# MainMCU.net
KiCad netlist of a schematic drawn in Altium Designer
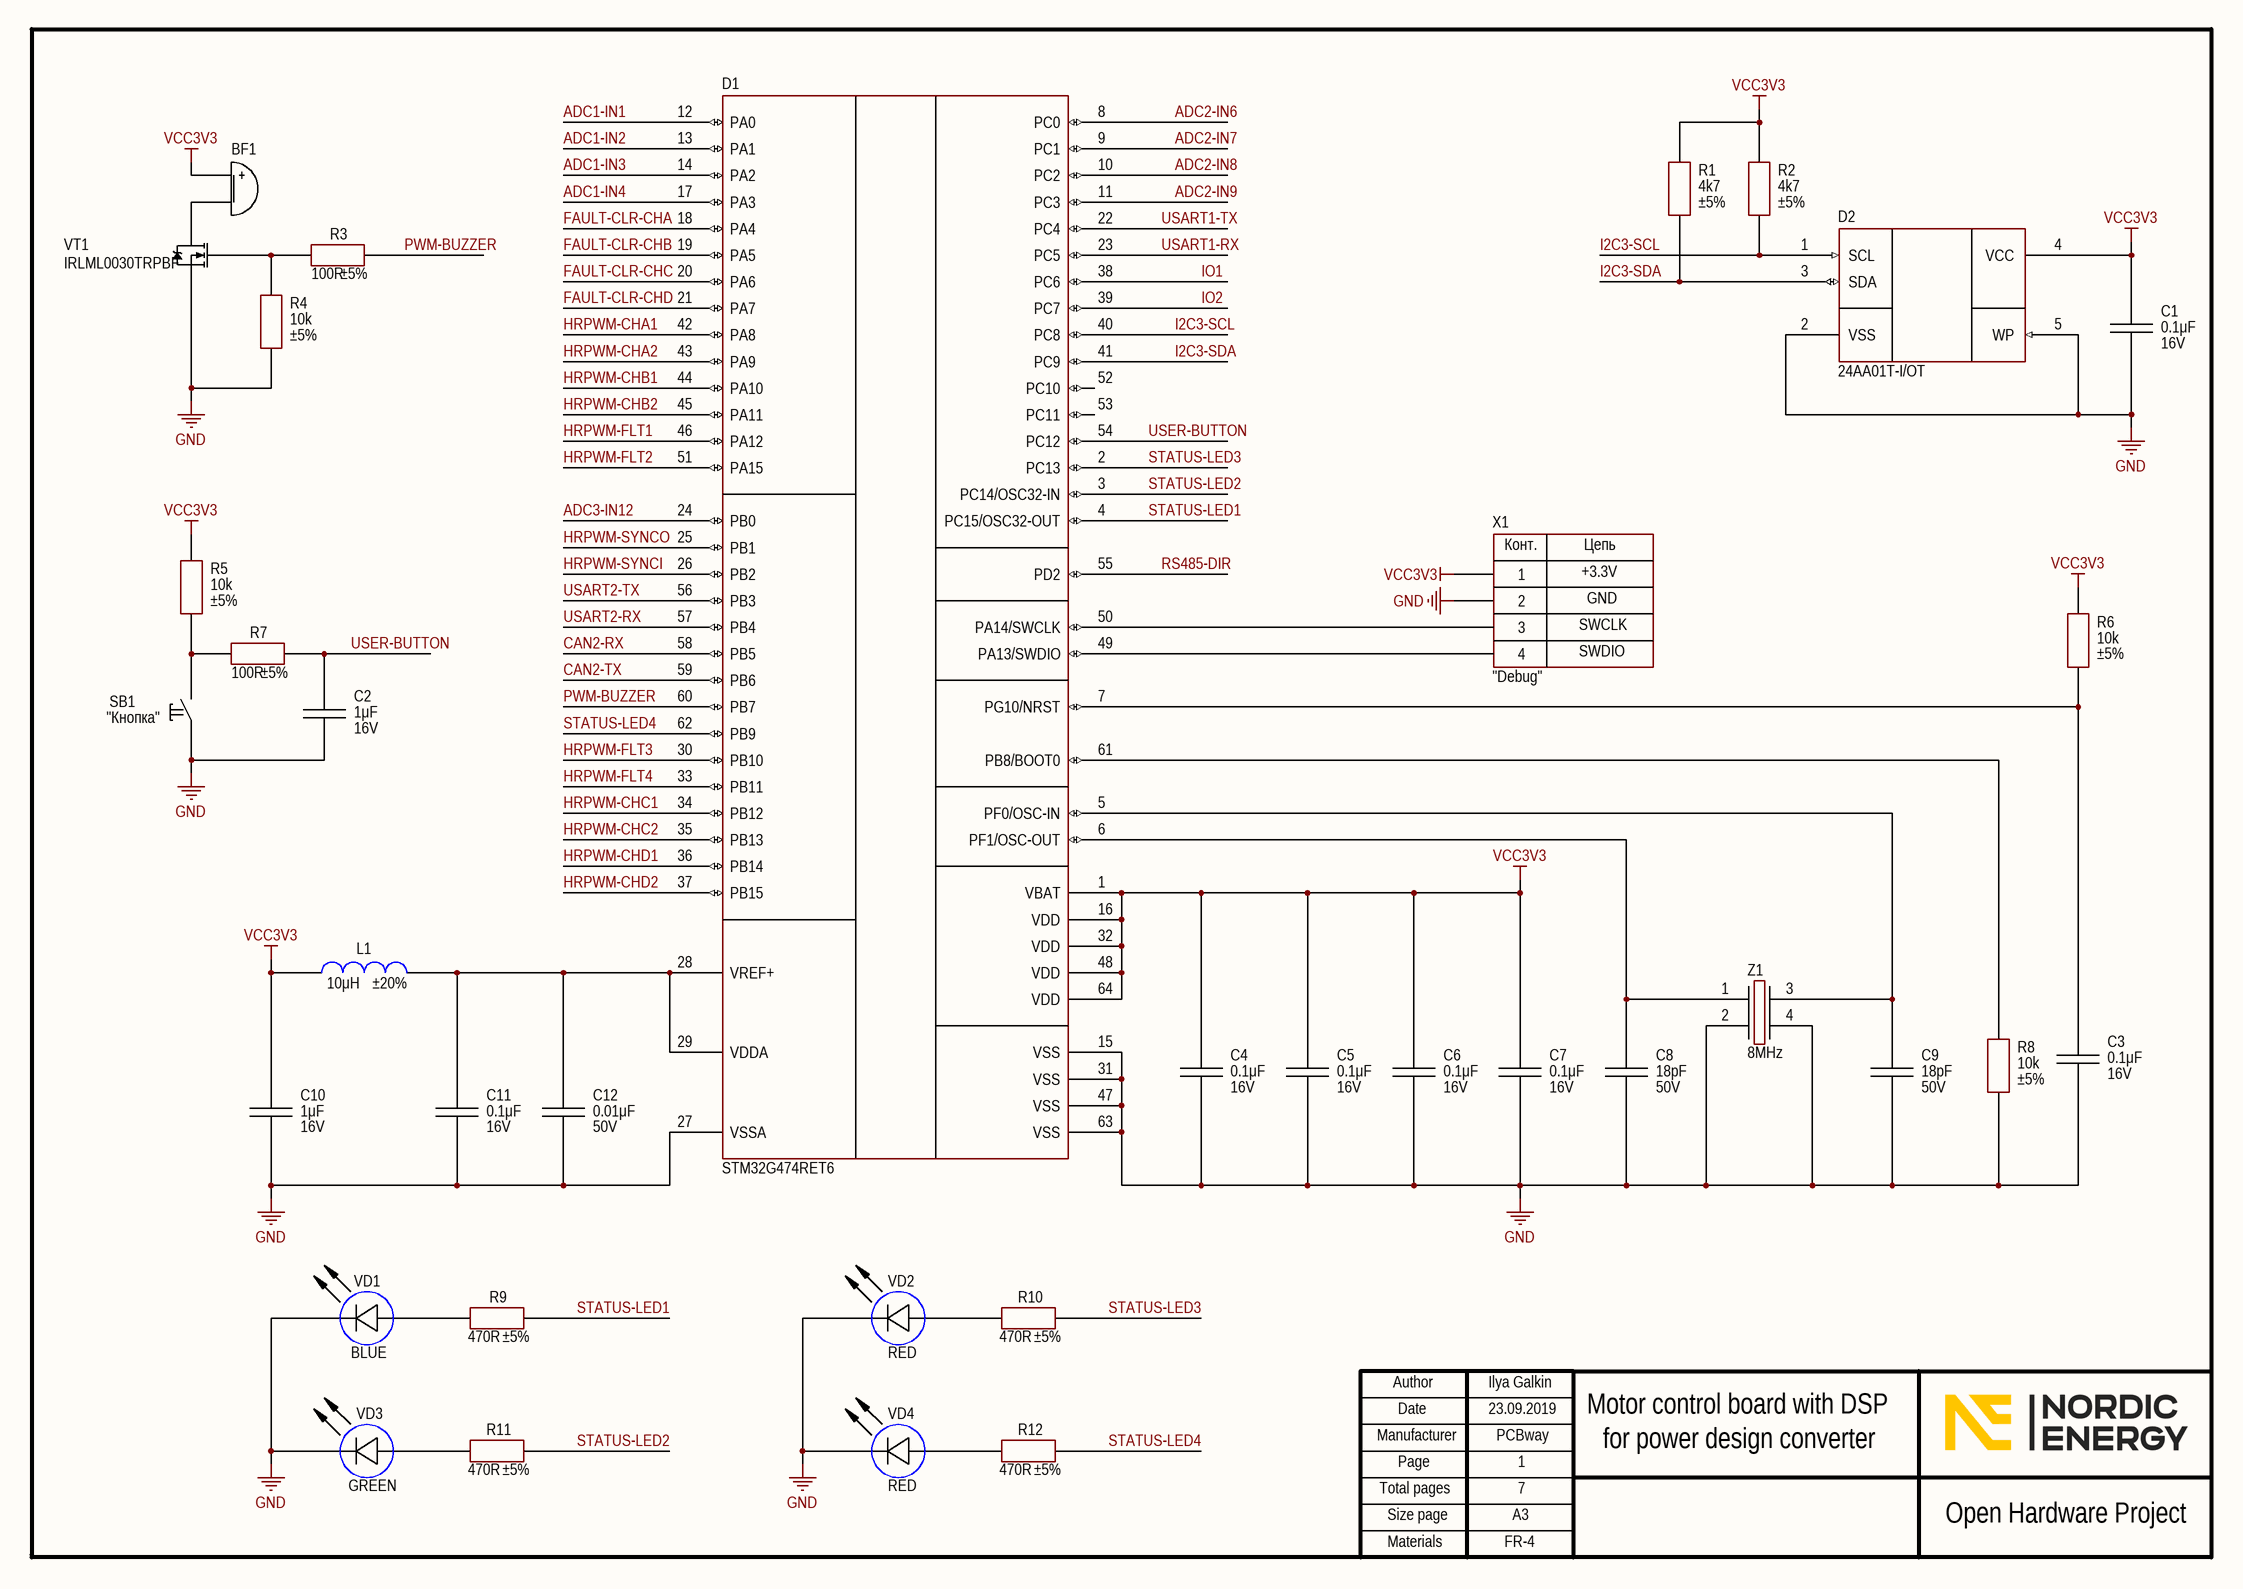
[diagram p0: MainMCU.SchDoc]

(export (version "E")
  (design (tool "Eeschema 10.0.6"))
  (components
    (comp (ref "BF1")
      (value "~")
      (footprint "BUZ: CMT-7525")
      (fields
        (field (name "MANUFACTURER") "PUI Audio")
        (field (name "VALUEMANUFACTURERPARTNUMBER") "DIP switch, 2.73 kHz, 3VDC, 80mA, -20...+70°C")
        (field (name "PARTNUMBER") "AT-0927-TT-6-R")
      )
      (libsource (lib "Electromechanics") (part "Buzzer"))
    )
    (comp (ref "C1")
      (value "0.1μF")
      (footprint "CAP: 0805")
      (fields
        (field (name "MANUFACTURER") "Yageo")
        (field (name "PARTNUMBER") "CC0805KRX7R7BB104")
        (field (name "VALUEMANUFACTURERPARTNUMBER") "Ceramic capacitor, 0.1μF, X7R, ±10%, 16V, 0805, -55...+125°C")
        (field (name "VOLTAGE") "16V")
      )
      (libsource (lib "Capacitor") (part "Ceramic_0805"))
    )
    (comp (ref "C2")
      (value "1μF")
      (footprint "CAP: 0805")
      (fields
        (field (name "MANUFACTURER") "Yageo")
        (field (name "PARTNUMBER") "CC0805KKX7R7BB105")
        (field (name "VALUEMANUFACTURERPARTNUMBER") "Ceramic capacitor, 1μF, X7R, ±10%, 16V, 0805, -55...+125°C")
        (field (name "VOLTAGE") "16V")
      )
      (libsource (lib "Capacitor") (part "Ceramic_0805"))
    )
    (comp (ref "C3")
      (value "0.1μF")
      (footprint "CAP: 0805")
      (fields
        (field (name "MANUFACTURER") "Yageo")
        (field (name "PARTNUMBER") "CC0805KRX7R7BB104")
        (field (name "VALUEMANUFACTURERPARTNUMBER") "Ceramic capacitor, 0.1μF, X7R, ±10%, 16V, 0805, -55...+125°C")
        (field (name "VOLTAGE") "16V")
      )
      (libsource (lib "Capacitor") (part "Ceramic_0805"))
    )
    (comp (ref "C4")
      (value "0.1μF")
      (footprint "CAP: 0805")
      (fields
        (field (name "MANUFACTURER") "Yageo")
        (field (name "PARTNUMBER") "CC0805KRX7R7BB104")
        (field (name "VALUEMANUFACTURERPARTNUMBER") "Ceramic capacitor, 0.1μF, X7R, ±10%, 16V, 0805, -55...+125°C")
        (field (name "VOLTAGE") "16V")
      )
      (libsource (lib "Capacitor") (part "Ceramic_0805"))
    )
    (comp (ref "C5")
      (value "0.1μF")
      (footprint "CAP: 0805")
      (fields
        (field (name "MANUFACTURER") "Yageo")
        (field (name "PARTNUMBER") "CC0805KRX7R7BB104")
        (field (name "VALUEMANUFACTURERPARTNUMBER") "Ceramic capacitor, 0.1μF, X7R, ±10%, 16V, 0805, -55...+125°C")
        (field (name "VOLTAGE") "16V")
      )
      (libsource (lib "Capacitor") (part "Ceramic_0805"))
    )
    (comp (ref "C6")
      (value "0.1μF")
      (footprint "CAP: 0805")
      (fields
        (field (name "MANUFACTURER") "Yageo")
        (field (name "PARTNUMBER") "CC0805KRX7R7BB104")
        (field (name "VALUEMANUFACTURERPARTNUMBER") "Ceramic capacitor, 0.1μF, X7R, ±10%, 16V, 0805, -55...+125°C")
        (field (name "VOLTAGE") "16V")
      )
      (libsource (lib "Capacitor") (part "Ceramic_0805"))
    )
    (comp (ref "C7")
      (value "0.1μF")
      (footprint "CAP: 0805")
      (fields
        (field (name "MANUFACTURER") "Yageo")
        (field (name "PARTNUMBER") "CC0805KRX7R7BB104")
        (field (name "VALUEMANUFACTURERPARTNUMBER") "Ceramic capacitor, 0.1μF, X7R, ±10%, 16V, 0805, -55...+125°C")
        (field (name "VOLTAGE") "16V")
      )
      (libsource (lib "Capacitor") (part "Ceramic_0805"))
    )
    (comp (ref "C8")
      (value "18pF")
      (footprint "CAP: 0805")
      (fields
        (field (name "MANUFACTURER") "Yageo")
        (field (name "PARTNUMBER") "CC0805JRNPO9BN180")
        (field (name "VALUEMANUFACTURERPARTNUMBER") "Ceramic capacitor, 18pF, NPO, ±10%, 50V, 0805, -55...+125°C")
        (field (name "VOLTAGE") "50V")
      )
      (libsource (lib "Capacitor") (part "Ceramic_0805"))
    )
    (comp (ref "C9")
      (value "18pF")
      (footprint "CAP: 0805")
      (fields
        (field (name "MANUFACTURER") "Yageo")
        (field (name "PARTNUMBER") "CC0805JRNPO9BN180")
        (field (name "VALUEMANUFACTURERPARTNUMBER") "Ceramic capacitor, 18pF, NPO, ±10%, 50V, 0805, -55...+125°C")
        (field (name "VOLTAGE") "50V")
      )
      (libsource (lib "Capacitor") (part "Ceramic_0805"))
    )
    (comp (ref "C10")
      (value "1μF")
      (footprint "CAP: 0805")
      (fields
        (field (name "MANUFACTURER") "Yageo")
        (field (name "PARTNUMBER") "CC0805KKX7R7BB105")
        (field (name "VALUEMANUFACTURERPARTNUMBER") "Ceramic capacitor, 1μF, X7R, ±10%, 16V, 0805, -55...+125°C")
        (field (name "VOLTAGE") "16V")
      )
      (libsource (lib "Capacitor") (part "Ceramic_0805"))
    )
    (comp (ref "C11")
      (value "0.1μF")
      (footprint "CAP: 0805")
      (fields
        (field (name "MANUFACTURER") "Yageo")
        (field (name "PARTNUMBER") "CC0805KRX7R7BB104")
        (field (name "VALUEMANUFACTURERPARTNUMBER") "Ceramic capacitor, 0.1μF, X7R, ±10%, 16V, 0805, -55...+125°C")
        (field (name "VOLTAGE") "16V")
      )
      (libsource (lib "Capacitor") (part "Ceramic_0805"))
    )
    (comp (ref "C12")
      (value "0.01μF")
      (footprint "CAP: 0805")
      (fields
        (field (name "MANUFACTURER") "Yageo")
        (field (name "PARTNUMBER") "CC0805KRX7R9BB103")
        (field (name "VALUEMANUFACTURERPARTNUMBER") "Ceramic capacitor, 0.01μF, X7R, ±10%, 50V, 0805, -55...+125°C")
        (field (name "VOLTAGE") "50V")
      )
      (libsource (lib "Capacitor") (part "Ceramic_0805"))
    )
    (comp (ref "D1")
      (value "~")
      (footprint "64-LQFP")
      (description "Cortex-M4")
      (fields
        (field (name "MANUFACTURER") "STMicroelectronics")
        (field (name "VALUEMANUFACTURERPARTNUMBER") "IC microcontroller, 32-Bit, Cortex-M4, 170MHz, 512KB, 128KB, 1.71...3.6V, -40...+85°C, 64-LQFP")
        (field (name "PARTNUMBER") "STM32G474RET6")
      )
      (libsource (lib "IC. MCU") (part "STM32G474RET6"))
    )
    (comp (ref "D2")
      (value "~")
      (footprint "SOT23-5")
      (description "EEPROM")
      (fields
        (field (name "MANUFACTURER") "Microchip Technology")
        (field (name "VALUEMANUFACTURERPARTNUMBER") "IC memory, EEPROM, 1KB (128x8), 400 kHz, I2C, 1.7...5.5V, -40...+85°C, SOT-23-5")
        (field (name "PARTNUMBER") "24AA01T-I/OT")
      )
      (libsource (lib "IC. Memory") (part "24AA01T"))
    )
    (comp (ref "L1")
      (value "10μH")
      (footprint "IND: 0805")
      (fields
        (field (name "MANUFACTURER") "Murata Electronics")
        (field (name "PARTNUMBER") "LQM21FN100M70L")
        (field (name "VALUEMANUFACTURERPARTNUMBER") "Fixed inductor, 10μH, ±20%, 0805, 100mA, -55...+125°C")
        (field (name "TOLERANCE") "±20%")
      )
      (libsource (lib "Inductor") (part "Inductor_0805"))
    )
    (comp (ref "R1")
      (value "4k7")
      (footprint "RES: 0805")
      (fields
        (field (name "MANUFACTURER") "Yageo")
        (field (name "PARTNUMBER") "RC0805JR-074K7L")
        (field (name "VALUEMANUFACTURERPARTNUMBER") "Resistor film, 4k7, ±5%, 0805, 0.125W, -55...+125°C")
        (field (name "TOLERANCE") "±5%")
      )
      (libsource (lib "Resistor") (part "Resistor_0805"))
    )
    (comp (ref "R2")
      (value "4k7")
      (footprint "RES: 0805")
      (fields
        (field (name "MANUFACTURER") "Yageo")
        (field (name "PARTNUMBER") "RC0805JR-074K7L")
        (field (name "VALUEMANUFACTURERPARTNUMBER") "Resistor film, 4k7, ±5%, 0805, 0.125W, -55...+125°C")
        (field (name "TOLERANCE") "±5%")
      )
      (libsource (lib "Resistor") (part "Resistor_0805"))
    )
    (comp (ref "R3")
      (value "100R")
      (footprint "RES: 0805")
      (fields
        (field (name "MANUFACTURER") "Yageo")
        (field (name "PARTNUMBER") "RC0805JR-07100RL")
        (field (name "VALUEMANUFACTURERPARTNUMBER") "Resistor film, 100R, ±5%, 0805, 0.125W, -55...+125°C")
        (field (name "TOLERANCE") "±5%")
      )
      (libsource (lib "") (part "Resistor_0805_1"))
    )
    (comp (ref "R4")
      (value "10k")
      (footprint "RES: 0805")
      (fields
        (field (name "MANUFACTURER") "Yageo")
        (field (name "PARTNUMBER") "RC0805JR-0710KL")
        (field (name "VALUEMANUFACTURERPARTNUMBER") "Resistor film, 10k, ±5%, 0805, 0.125W, -55...+125°C")
        (field (name "TOLERANCE") "±5%")
      )
      (libsource (lib "Resistor") (part "Resistor_0805"))
    )
    (comp (ref "R5")
      (value "10k")
      (footprint "RES: 0805")
      (fields
        (field (name "MANUFACTURER") "Yageo")
        (field (name "PARTNUMBER") "RC0805JR-0710KL")
        (field (name "VALUEMANUFACTURERPARTNUMBER") "Resistor film, 10k, ±5%, 0805, 0.125W, -55...+125°C")
        (field (name "TOLERANCE") "±5%")
      )
      (libsource (lib "Resistor") (part "Resistor_0805"))
    )
    (comp (ref "R6")
      (value "10k")
      (footprint "RES: 0805")
      (fields
        (field (name "MANUFACTURER") "Yageo")
        (field (name "PARTNUMBER") "RC0805JR-0710KL")
        (field (name "VALUEMANUFACTURERPARTNUMBER") "Resistor film, 10k, ±5%, 0805, 0.125W, -55...+125°C")
        (field (name "TOLERANCE") "±5%")
      )
      (libsource (lib "Resistor") (part "Resistor_0805"))
    )
    (comp (ref "R7")
      (value "100R")
      (footprint "RES: 0805")
      (fields
        (field (name "MANUFACTURER") "Yageo")
        (field (name "PARTNUMBER") "RC0805JR-07100RL")
        (field (name "VALUEMANUFACTURERPARTNUMBER") "Resistor film, 100R, ±5%, 0805, 0.125W, -55...+125°C")
        (field (name "TOLERANCE") "±5%")
      )
      (libsource (lib "") (part "Resistor_0805_1"))
    )
    (comp (ref "R8")
      (value "10k")
      (footprint "RES: 0805")
      (fields
        (field (name "MANUFACTURER") "Yageo")
        (field (name "PARTNUMBER") "RC0805JR-0710KL")
        (field (name "VALUEMANUFACTURERPARTNUMBER") "Resistor film, 10k, ±5%, 0805, 0.125W, -55...+125°C")
        (field (name "TOLERANCE") "±5%")
      )
      (libsource (lib "Resistor") (part "Resistor_0805"))
    )
    (comp (ref "R9")
      (value "470R")
      (footprint "RES: 0805")
      (fields
        (field (name "MANUFACTURER") "Yageo")
        (field (name "PARTNUMBER") "RC0805JR-07470RL")
        (field (name "VALUEMANUFACTURERPARTNUMBER") "Resistor film, 470R, ±5%, 0805, 0.125W, -55...+125°C")
        (field (name "TOLERANCE") "±5%")
      )
      (libsource (lib "") (part "Resistor_0805_1"))
    )
    (comp (ref "R10")
      (value "470R")
      (footprint "RES: 0805")
      (fields
        (field (name "MANUFACTURER") "Yageo")
        (field (name "PARTNUMBER") "RC0805JR-07470RL")
        (field (name "VALUEMANUFACTURERPARTNUMBER") "Resistor film, 470R, ±5%, 0805, 0.125W, -55...+125°C")
        (field (name "TOLERANCE") "±5%")
      )
      (libsource (lib "") (part "Resistor_0805_1"))
    )
    (comp (ref "R11")
      (value "470R")
      (footprint "RES: 0805")
      (fields
        (field (name "MANUFACTURER") "Yageo")
        (field (name "PARTNUMBER") "RC0805JR-07470RL")
        (field (name "VALUEMANUFACTURERPARTNUMBER") "Resistor film, 470R, ±5%, 0805, 0.125W, -55...+125°C")
        (field (name "TOLERANCE") "±5%")
      )
      (libsource (lib "") (part "Resistor_0805_1"))
    )
    (comp (ref "R12")
      (value "470R")
      (footprint "RES: 0805")
      (fields
        (field (name "MANUFACTURER") "Yageo")
        (field (name "PARTNUMBER") "RC0805JR-07470RL")
        (field (name "VALUEMANUFACTURERPARTNUMBER") "Resistor film, 470R, ±5%, 0805, 0.125W, -55...+125°C")
        (field (name "TOLERANCE") "±5%")
      )
      (libsource (lib "") (part "Resistor_0805_1"))
    )
    (comp (ref "SB1")
      (value "~")
      (footprint "BUT: 6x6 SMD")
      (fields
        (field (name "MANUFACTURER") "TE Connectivity")
        (field (name "VALUEMANUFACTURERPARTNUMBER") "Tactile button, 6x6mm")
        (field (name "PARTNUMBER") "FSM2JSMAATR")
        (field (name "COMMENTTEXT") "\"Кнопка\"")
      )
      (libsource (lib "Electromechanics") (part "Button_tactile"))
    )
    (comp (ref "VD1")
      (value "~")
      (footprint "LED: 0805B")
      (fields
        (field (name "MANUFACTURER") "Wurth")
        (field (name "VALUEMANUFACTURERPARTNUMBER") "LED, 20mA, 3.2V, 0805, -55...+150°C")
        (field (name "PARTNUMBER") "150080BS75000")
        (field (name "COLOR") "BLUE")
      )
      (libsource (lib "Diode") (part "LED_single"))
    )
    (comp (ref "VD2")
      (value "~")
      (footprint "LED: 0805R")
      (fields
        (field (name "MANUFACTURER") "Wurth")
        (field (name "VALUEMANUFACTURERPARTNUMBER") "LED, 20mA, 2V, 0805, -55...+150°C")
        (field (name "PARTNUMBER") "150080RS75000")
        (field (name "COLOR") "RED")
      )
      (libsource (lib "Diode") (part "LED_single"))
    )
    (comp (ref "VD3")
      (value "~")
      (footprint "LED: 0805G")
      (fields
        (field (name "MANUFACTURER") "Wurth")
        (field (name "VALUEMANUFACTURERPARTNUMBER") "LED, 20mA, 2V, 0805, -55...+150°C")
        (field (name "PARTNUMBER") "150080VS75000")
        (field (name "COLOR") "GREEN")
      )
      (libsource (lib "Diode") (part "LED_single"))
    )
    (comp (ref "VD4")
      (value "~")
      (footprint "LED: 0805R")
      (fields
        (field (name "MANUFACTURER") "Wurth")
        (field (name "VALUEMANUFACTURERPARTNUMBER") "LED, 20mA, 2V, 0805, -55...+150°C")
        (field (name "PARTNUMBER") "150080RS75000")
        (field (name "COLOR") "RED")
      )
      (libsource (lib "Diode") (part "LED_single"))
    )
    (comp (ref "VT1")
      (value "~")
      (footprint "SOT23")
      (fields
        (field (name "MANUFACTURER") "Infineon Technologies")
        (field (name "VALUEMANUFACTURERPARTNUMBER") "MOSFET N-channel transistor, 30V, 5.3A, 2.6nC, 2.5W, 27mOhm, 382pF, SOT-23, -55...+150°C")
        (field (name "PARTNUMBER") "IRLML0030TRPBF")
      )
      (libsource (lib "Transistor") (part "MOSFET_N_132"))
    )
    (comp (ref "X1")
      (value "~")
      (footprint "CON: SM04B-GHS")
      (fields
        (field (name "MANUFACTURER") "JST")
        (field (name "VALUEMANUFACTURERPARTNUMBER") "Connector, 4pin, 1.25mm, 50VDC, 1A")
        (field (name "PARTNUMBER") "SM04B-GHS")
        (field (name "COMMENTTEXT") "\"Debug\"")
      )
      (libsource (lib "Connector") (part "Connector_SM04B"))
    )
    (comp (ref "Z1")
      (value "~")
      (footprint "OSC: 5032")
      (fields
        (field (name "MANUFACTURER") "Diodes Incorporated")
        (field (name "PARTNUMBER") "ABM3B-8.000MHZ-B2-T")
        (field (name "VALUEMANUFACTURERPARTNUMBER") "Crystal, 8MHz, 18pF, ±30ppm, case 5032, -20...+70°C")
        (field (name "FREQUENCY") "8MHz")
      )
      (libsource (lib "Oscilator") (part "Crystal_5032"))
    )
  )
  (nets
    (net (code "1") (name "/ADC1-IN1") (class "Default")
      (node (ref "D1") (pin "12") (pinfunction "PA0_12") (pintype "bidirectional"))
    )
    (net (code "2") (name "/ADC1-IN2") (class "Default")
      (node (ref "D1") (pin "13") (pinfunction "PA1_13") (pintype "bidirectional"))
    )
    (net (code "3") (name "/ADC1-IN3") (class "Default")
      (node (ref "D1") (pin "14") (pinfunction "PA2_14") (pintype "bidirectional"))
    )
    (net (code "4") (name "/ADC1-IN4") (class "Default")
      (node (ref "D1") (pin "17") (pinfunction "PA3_17") (pintype "bidirectional"))
    )
    (net (code "5") (name "/ADC2-IN6") (class "Default")
      (node (ref "D1") (pin "8") (pinfunction "PC0_8") (pintype "bidirectional"))
    )
    (net (code "6") (name "/ADC2-IN7") (class "Default")
      (node (ref "D1") (pin "9") (pinfunction "PC1_9") (pintype "bidirectional"))
    )
    (net (code "7") (name "/ADC2-IN8") (class "Default")
      (node (ref "D1") (pin "10") (pinfunction "PC2_10") (pintype "bidirectional"))
    )
    (net (code "8") (name "/ADC2-IN9") (class "Default")
      (node (ref "D1") (pin "11") (pinfunction "PC3_11") (pintype "bidirectional"))
    )
    (net (code "9") (name "/ADC3-IN12") (class "Default")
      (node (ref "D1") (pin "24") (pinfunction "PB0_24") (pintype "bidirectional"))
    )
    (net (code "10") (name "/CAN2-RX") (class "Default")
      (node (ref "D1") (pin "58") (pinfunction "PB5_58") (pintype "bidirectional"))
    )
    (net (code "11") (name "/CAN2-TX") (class "Default")
      (node (ref "D1") (pin "59") (pinfunction "PB6_59") (pintype "bidirectional"))
    )
    (net (code "12") (name "/FAULT-CLR-CHA") (class "Default")
      (node (ref "D1") (pin "18") (pinfunction "PA4_18") (pintype "bidirectional"))
    )
    (net (code "13") (name "/FAULT-CLR-CHB") (class "Default")
      (node (ref "D1") (pin "19") (pinfunction "PA5_19") (pintype "bidirectional"))
    )
    (net (code "14") (name "/FAULT-CLR-CHC") (class "Default")
      (node (ref "D1") (pin "20") (pinfunction "PA6_20") (pintype "bidirectional"))
    )
    (net (code "15") (name "/FAULT-CLR-CHD") (class "Default")
      (node (ref "D1") (pin "21") (pinfunction "PA7_21") (pintype "bidirectional"))
    )
    (net (code "16") (name "/HRPWM-CHA1") (class "Default")
      (node (ref "D1") (pin "42") (pinfunction "PA8_42") (pintype "bidirectional"))
    )
    (net (code "17") (name "/HRPWM-CHA2") (class "Default")
      (node (ref "D1") (pin "43") (pinfunction "PA9_43") (pintype "bidirectional"))
    )
    (net (code "18") (name "/HRPWM-CHB1") (class "Default")
      (node (ref "D1") (pin "44") (pinfunction "PA10_44") (pintype "bidirectional"))
    )
    (net (code "19") (name "/HRPWM-CHB2") (class "Default")
      (node (ref "D1") (pin "45") (pinfunction "PA11_45") (pintype "bidirectional"))
    )
    (net (code "20") (name "/HRPWM-CHC1") (class "Default")
      (node (ref "D1") (pin "34") (pinfunction "PB12_34") (pintype "bidirectional"))
    )
    (net (code "21") (name "/HRPWM-CHC2") (class "Default")
      (node (ref "D1") (pin "35") (pinfunction "PB13_35") (pintype "bidirectional"))
    )
    (net (code "22") (name "/HRPWM-CHD1") (class "Default")
      (node (ref "D1") (pin "36") (pinfunction "PB14_36") (pintype "bidirectional"))
    )
    (net (code "23") (name "/HRPWM-CHD2") (class "Default")
      (node (ref "D1") (pin "37") (pinfunction "PB15_37") (pintype "bidirectional"))
    )
    (net (code "24") (name "/HRPWM-FLT1") (class "Default")
      (node (ref "D1") (pin "46") (pinfunction "PA12_46") (pintype "bidirectional"))
    )
    (net (code "25") (name "/HRPWM-FLT2") (class "Default")
      (node (ref "D1") (pin "51") (pinfunction "PA15_51") (pintype "bidirectional"))
    )
    (net (code "26") (name "/HRPWM-FLT3") (class "Default")
      (node (ref "D1") (pin "30") (pinfunction "PB10_30") (pintype "bidirectional"))
    )
    (net (code "27") (name "/HRPWM-FLT4") (class "Default")
      (node (ref "D1") (pin "33") (pinfunction "PB11_33") (pintype "bidirectional"))
    )
    (net (code "28") (name "/HRPWM-SYNCI") (class "Default")
      (node (ref "D1") (pin "26") (pinfunction "PB2_26") (pintype "bidirectional"))
    )
    (net (code "29") (name "/HRPWM-SYNCO") (class "Default")
      (node (ref "D1") (pin "25") (pinfunction "PB1_25") (pintype "bidirectional"))
    )
    (net (code "30") (name "/I2C3-SCL") (class "Default")
      (node (ref "D1") (pin "40") (pinfunction "PC8_40") (pintype "bidirectional"))
      (node (ref "D2") (pin "1") (pinfunction "SCL_1") (pintype "input"))
      (node (ref "R2") (pin "2") (pinfunction "2_2") (pintype "passive"))
    )
    (net (code "31") (name "/I2C3-SDA") (class "Default")
      (node (ref "D1") (pin "41") (pinfunction "PC9_41") (pintype "bidirectional"))
      (node (ref "D2") (pin "3") (pinfunction "SDA_3") (pintype "bidirectional"))
      (node (ref "R1") (pin "2") (pinfunction "2_2") (pintype "passive"))
    )
    (net (code "32") (name "/IO1") (class "Default")
      (node (ref "D1") (pin "38") (pinfunction "PC6_38") (pintype "bidirectional"))
    )
    (net (code "33") (name "/IO2") (class "Default")
      (node (ref "D1") (pin "39") (pinfunction "PC7_39") (pintype "bidirectional"))
    )
    (net (code "34") (name "/PWM-BUZZER") (class "Default")
      (node (ref "D1") (pin "60") (pinfunction "PB7_60") (pintype "bidirectional"))
      (node (ref "R3") (pin "2") (pinfunction "2_2") (pintype "passive"))
    )
    (net (code "35") (name "/RS485-DIR") (class "Default")
      (node (ref "D1") (pin "55") (pinfunction "PD2_55") (pintype "bidirectional"))
    )
    (net (code "36") (name "/STATUS-LED1") (class "Default")
      (node (ref "D1") (pin "4") (pinfunction "PC15/OSC32-OUT_4") (pintype "bidirectional"))
      (node (ref "R9") (pin "2") (pinfunction "2_2") (pintype "passive"))
    )
    (net (code "37") (name "/STATUS-LED2") (class "Default")
      (node (ref "D1") (pin "3") (pinfunction "PC14/OSC32-IN_3") (pintype "bidirectional"))
      (node (ref "R11") (pin "2") (pinfunction "2_2") (pintype "passive"))
    )
    (net (code "38") (name "/STATUS-LED3") (class "Default")
      (node (ref "D1") (pin "2") (pinfunction "PC13_2") (pintype "bidirectional"))
      (node (ref "R10") (pin "2") (pinfunction "2_2") (pintype "passive"))
    )
    (net (code "39") (name "/STATUS-LED4") (class "Default")
      (node (ref "D1") (pin "62") (pinfunction "PB9_62") (pintype "bidirectional"))
      (node (ref "R12") (pin "2") (pinfunction "2_2") (pintype "passive"))
    )
    (net (code "40") (name "/USART1-RX") (class "Default")
      (node (ref "D1") (pin "23") (pinfunction "PC5_23") (pintype "bidirectional"))
    )
    (net (code "41") (name "/USART1-TX") (class "Default")
      (node (ref "D1") (pin "22") (pinfunction "PC4_22") (pintype "bidirectional"))
    )
    (net (code "42") (name "/USART2-RX") (class "Default")
      (node (ref "D1") (pin "57") (pinfunction "PB4_57") (pintype "bidirectional"))
    )
    (net (code "43") (name "/USART2-TX") (class "Default")
      (node (ref "D1") (pin "56") (pinfunction "PB3_56") (pintype "bidirectional"))
    )
    (net (code "44") (name "/USER-BUTTON") (class "Default")
      (node (ref "C2") (pin "2") (pinfunction "2_2") (pintype "power_in"))
      (node (ref "D1") (pin "54") (pinfunction "PC12_54") (pintype "bidirectional"))
      (node (ref "R7") (pin "2") (pinfunction "2_2") (pintype "passive"))
    )
    (net (code "45") (name "GND") (class "Default")
      (node (ref "C1") (pin "1") (pinfunction "1_1") (pintype "power_in"))
      (node (ref "C10") (pin "1") (pinfunction "1_1") (pintype "power_in"))
      (node (ref "C11") (pin "1") (pinfunction "1_1") (pintype "power_in"))
      (node (ref "C12") (pin "1") (pinfunction "1_1") (pintype "power_in"))
      (node (ref "C2") (pin "1") (pinfunction "1_1") (pintype "power_in"))
      (node (ref "C3") (pin "1") (pinfunction "1_1") (pintype "power_in"))
      (node (ref "C4") (pin "1") (pinfunction "1_1") (pintype "power_in"))
      (node (ref "C5") (pin "1") (pinfunction "1_1") (pintype "power_in"))
      (node (ref "C6") (pin "1") (pinfunction "1_1") (pintype "power_in"))
      (node (ref "C7") (pin "1") (pinfunction "1_1") (pintype "power_in"))
      (node (ref "C8") (pin "1") (pinfunction "1_1") (pintype "power_in"))
      (node (ref "C9") (pin "1") (pinfunction "1_1") (pintype "power_in"))
      (node (ref "D1") (pin "15") (pinfunction "VSS_15") (pintype "passive"))
      (node (ref "D1") (pin "27") (pinfunction "VSSA_27") (pintype "passive"))
      (node (ref "D1") (pin "31") (pinfunction "VSS_31") (pintype "passive"))
      (node (ref "D1") (pin "47") (pinfunction "VSS_47") (pintype "passive"))
      (node (ref "D1") (pin "63") (pinfunction "VSS_63") (pintype "passive"))
      (node (ref "D2") (pin "2") (pinfunction "VSS_2") (pintype "power_in"))
      (node (ref "D2") (pin "5") (pinfunction "WP_5") (pintype "input"))
      (node (ref "R4") (pin "2") (pinfunction "2_2") (pintype "passive"))
      (node (ref "R8") (pin "2") (pinfunction "2_2") (pintype "passive"))
      (node (ref "SB1") (pin "1") (pinfunction "1_1") (pintype "passive"))
      (node (ref "VD1") (pin "2") (pinfunction "C_2") (pintype "passive"))
      (node (ref "VD2") (pin "2") (pinfunction "C_2") (pintype "passive"))
      (node (ref "VD3") (pin "2") (pinfunction "C_2") (pintype "passive"))
      (node (ref "VD4") (pin "2") (pinfunction "C_2") (pintype "passive"))
      (node (ref "VT1") (pin "2") (pinfunction "S_2") (pintype "passive"))
      (node (ref "X1") (pin "2") (pinfunction "2_2") (pintype "passive"))
      (node (ref "Z1") (pin "2") (pinfunction "2_2") (pintype "passive"))
      (node (ref "Z1") (pin "4") (pinfunction "4_4") (pintype "passive"))
    )
    (net (code "46") (name "Net-(BF1--)") (class "Default")
      (node (ref "BF1") (pin "2") (pinfunction "-_2") (pintype "passive"))
      (node (ref "VT1") (pin "3") (pinfunction "D_3") (pintype "passive"))
    )
    (net (code "47") (name "Net-(D1-PA13{slash}SWDIO)") (class "Default")
      (node (ref "D1") (pin "49") (pinfunction "PA13/SWDIO_49") (pintype "bidirectional"))
      (node (ref "X1") (pin "4") (pinfunction "4_4") (pintype "power_in"))
    )
    (net (code "48") (name "Net-(D1-PA14{slash}SWCLK)") (class "Default")
      (node (ref "D1") (pin "50") (pinfunction "PA14/SWCLK_50") (pintype "bidirectional"))
      (node (ref "X1") (pin "3") (pinfunction "3_3") (pintype "power_in"))
    )
    (net (code "49") (name "Net-(D1-PB8{slash}BOOT0)") (class "Default")
      (node (ref "D1") (pin "61") (pinfunction "PB8/BOOT0_61") (pintype "bidirectional"))
      (node (ref "R8") (pin "1") (pinfunction "1_1") (pintype "passive"))
    )
    (net (code "50") (name "Net-(D1-PF0{slash}OSC-IN)") (class "Default")
      (node (ref "C9") (pin "2") (pinfunction "2_2") (pintype "power_in"))
      (node (ref "D1") (pin "5") (pinfunction "PF0/OSC-IN_5") (pintype "bidirectional"))
      (node (ref "Z1") (pin "3") (pinfunction "3_3") (pintype "passive"))
    )
    (net (code "51") (name "Net-(D1-PF1{slash}OSC-OUT)") (class "Default")
      (node (ref "C8") (pin "2") (pinfunction "2_2") (pintype "power_in"))
      (node (ref "D1") (pin "6") (pinfunction "PF1/OSC-OUT_6") (pintype "bidirectional"))
      (node (ref "Z1") (pin "1") (pinfunction "1_1") (pintype "passive"))
    )
    (net (code "52") (name "Net-(D1-PG10{slash}NRST)") (class "Default")
      (node (ref "C3") (pin "2") (pinfunction "2_2") (pintype "power_in"))
      (node (ref "D1") (pin "7") (pinfunction "PG10/NRST_7") (pintype "bidirectional"))
      (node (ref "R6") (pin "2") (pinfunction "2_2") (pintype "passive"))
    )
    (net (code "53") (name "Net-(D1-VDDA)") (class "Default")
      (node (ref "C11") (pin "2") (pinfunction "2_2") (pintype "power_in"))
      (node (ref "C12") (pin "2") (pinfunction "2_2") (pintype "power_in"))
      (node (ref "D1") (pin "28") (pinfunction "VREF+_28") (pintype "passive"))
      (node (ref "D1") (pin "29") (pinfunction "VDDA_29") (pintype "passive"))
      (node (ref "L1") (pin "1") (pinfunction "1_1") (pintype "passive"))
    )
    (net (code "54") (name "Net-(R5-Pad2)") (class "Default")
      (node (ref "R5") (pin "2") (pinfunction "2_2") (pintype "passive"))
      (node (ref "R7") (pin "1") (pinfunction "1_1") (pintype "passive"))
      (node (ref "SB1") (pin "2") (pinfunction "2_2") (pintype "passive"))
    )
    (net (code "55") (name "Net-(VD1-A)") (class "Default")
      (node (ref "R9") (pin "1") (pinfunction "1_1") (pintype "passive"))
      (node (ref "VD1") (pin "1") (pinfunction "A_1") (pintype "passive"))
    )
    (net (code "56") (name "Net-(VD2-A)") (class "Default")
      (node (ref "R10") (pin "1") (pinfunction "1_1") (pintype "passive"))
      (node (ref "VD2") (pin "1") (pinfunction "A_1") (pintype "passive"))
    )
    (net (code "57") (name "Net-(VD3-A)") (class "Default")
      (node (ref "R11") (pin "1") (pinfunction "1_1") (pintype "passive"))
      (node (ref "VD3") (pin "1") (pinfunction "A_1") (pintype "passive"))
    )
    (net (code "58") (name "Net-(VD4-A)") (class "Default")
      (node (ref "R12") (pin "1") (pinfunction "1_1") (pintype "passive"))
      (node (ref "VD4") (pin "1") (pinfunction "A_1") (pintype "passive"))
    )
    (net (code "59") (name "Net-(VT1-G)") (class "Default")
      (node (ref "R3") (pin "1") (pinfunction "1_1") (pintype "passive"))
      (node (ref "R4") (pin "1") (pinfunction "1_1") (pintype "passive"))
      (node (ref "VT1") (pin "1") (pinfunction "G_1") (pintype "passive"))
    )
    (net (code "60") (name "VCC3V3") (class "Default")
      (node (ref "BF1") (pin "1") (pinfunction "+_1") (pintype "passive"))
      (node (ref "C1") (pin "2") (pinfunction "2_2") (pintype "power_in"))
      (node (ref "C10") (pin "2") (pinfunction "2_2") (pintype "power_in"))
      (node (ref "C4") (pin "2") (pinfunction "2_2") (pintype "power_in"))
      (node (ref "C5") (pin "2") (pinfunction "2_2") (pintype "power_in"))
      (node (ref "C6") (pin "2") (pinfunction "2_2") (pintype "power_in"))
      (node (ref "C7") (pin "2") (pinfunction "2_2") (pintype "power_in"))
      (node (ref "D1") (pin "1") (pinfunction "VBAT_1") (pintype "passive"))
      (node (ref "D1") (pin "16") (pinfunction "VDD_16") (pintype "passive"))
      (node (ref "D1") (pin "32") (pinfunction "VDD_32") (pintype "passive"))
      (node (ref "D1") (pin "48") (pinfunction "VDD_48") (pintype "passive"))
      (node (ref "D1") (pin "64") (pinfunction "VDD_64") (pintype "passive"))
      (node (ref "D2") (pin "4") (pinfunction "VCC_4") (pintype "power_in"))
      (node (ref "L1") (pin "2") (pinfunction "2_2") (pintype "passive"))
      (node (ref "R1") (pin "1") (pinfunction "1_1") (pintype "passive"))
      (node (ref "R2") (pin "1") (pinfunction "1_1") (pintype "passive"))
      (node (ref "R5") (pin "1") (pinfunction "1_1") (pintype "passive"))
      (node (ref "R6") (pin "1") (pinfunction "1_1") (pintype "passive"))
      (node (ref "X1") (pin "1") (pinfunction "1_1") (pintype "passive"))
    )
    (net (code "61") (name "unconnected-(D1-PC10-Pad52)") (class "Default")
      (node (ref "D1") (pin "52") (pinfunction "PC10_52") (pintype "bidirectional"))
    )
    (net (code "62") (name "unconnected-(D1-PC11-Pad53)") (class "Default")
      (node (ref "D1") (pin "53") (pinfunction "PC11_53") (pintype "bidirectional"))
    )
  )
)
